# PCB.net
KiCad netlist of a schematic drawn in EasyEDA Pro
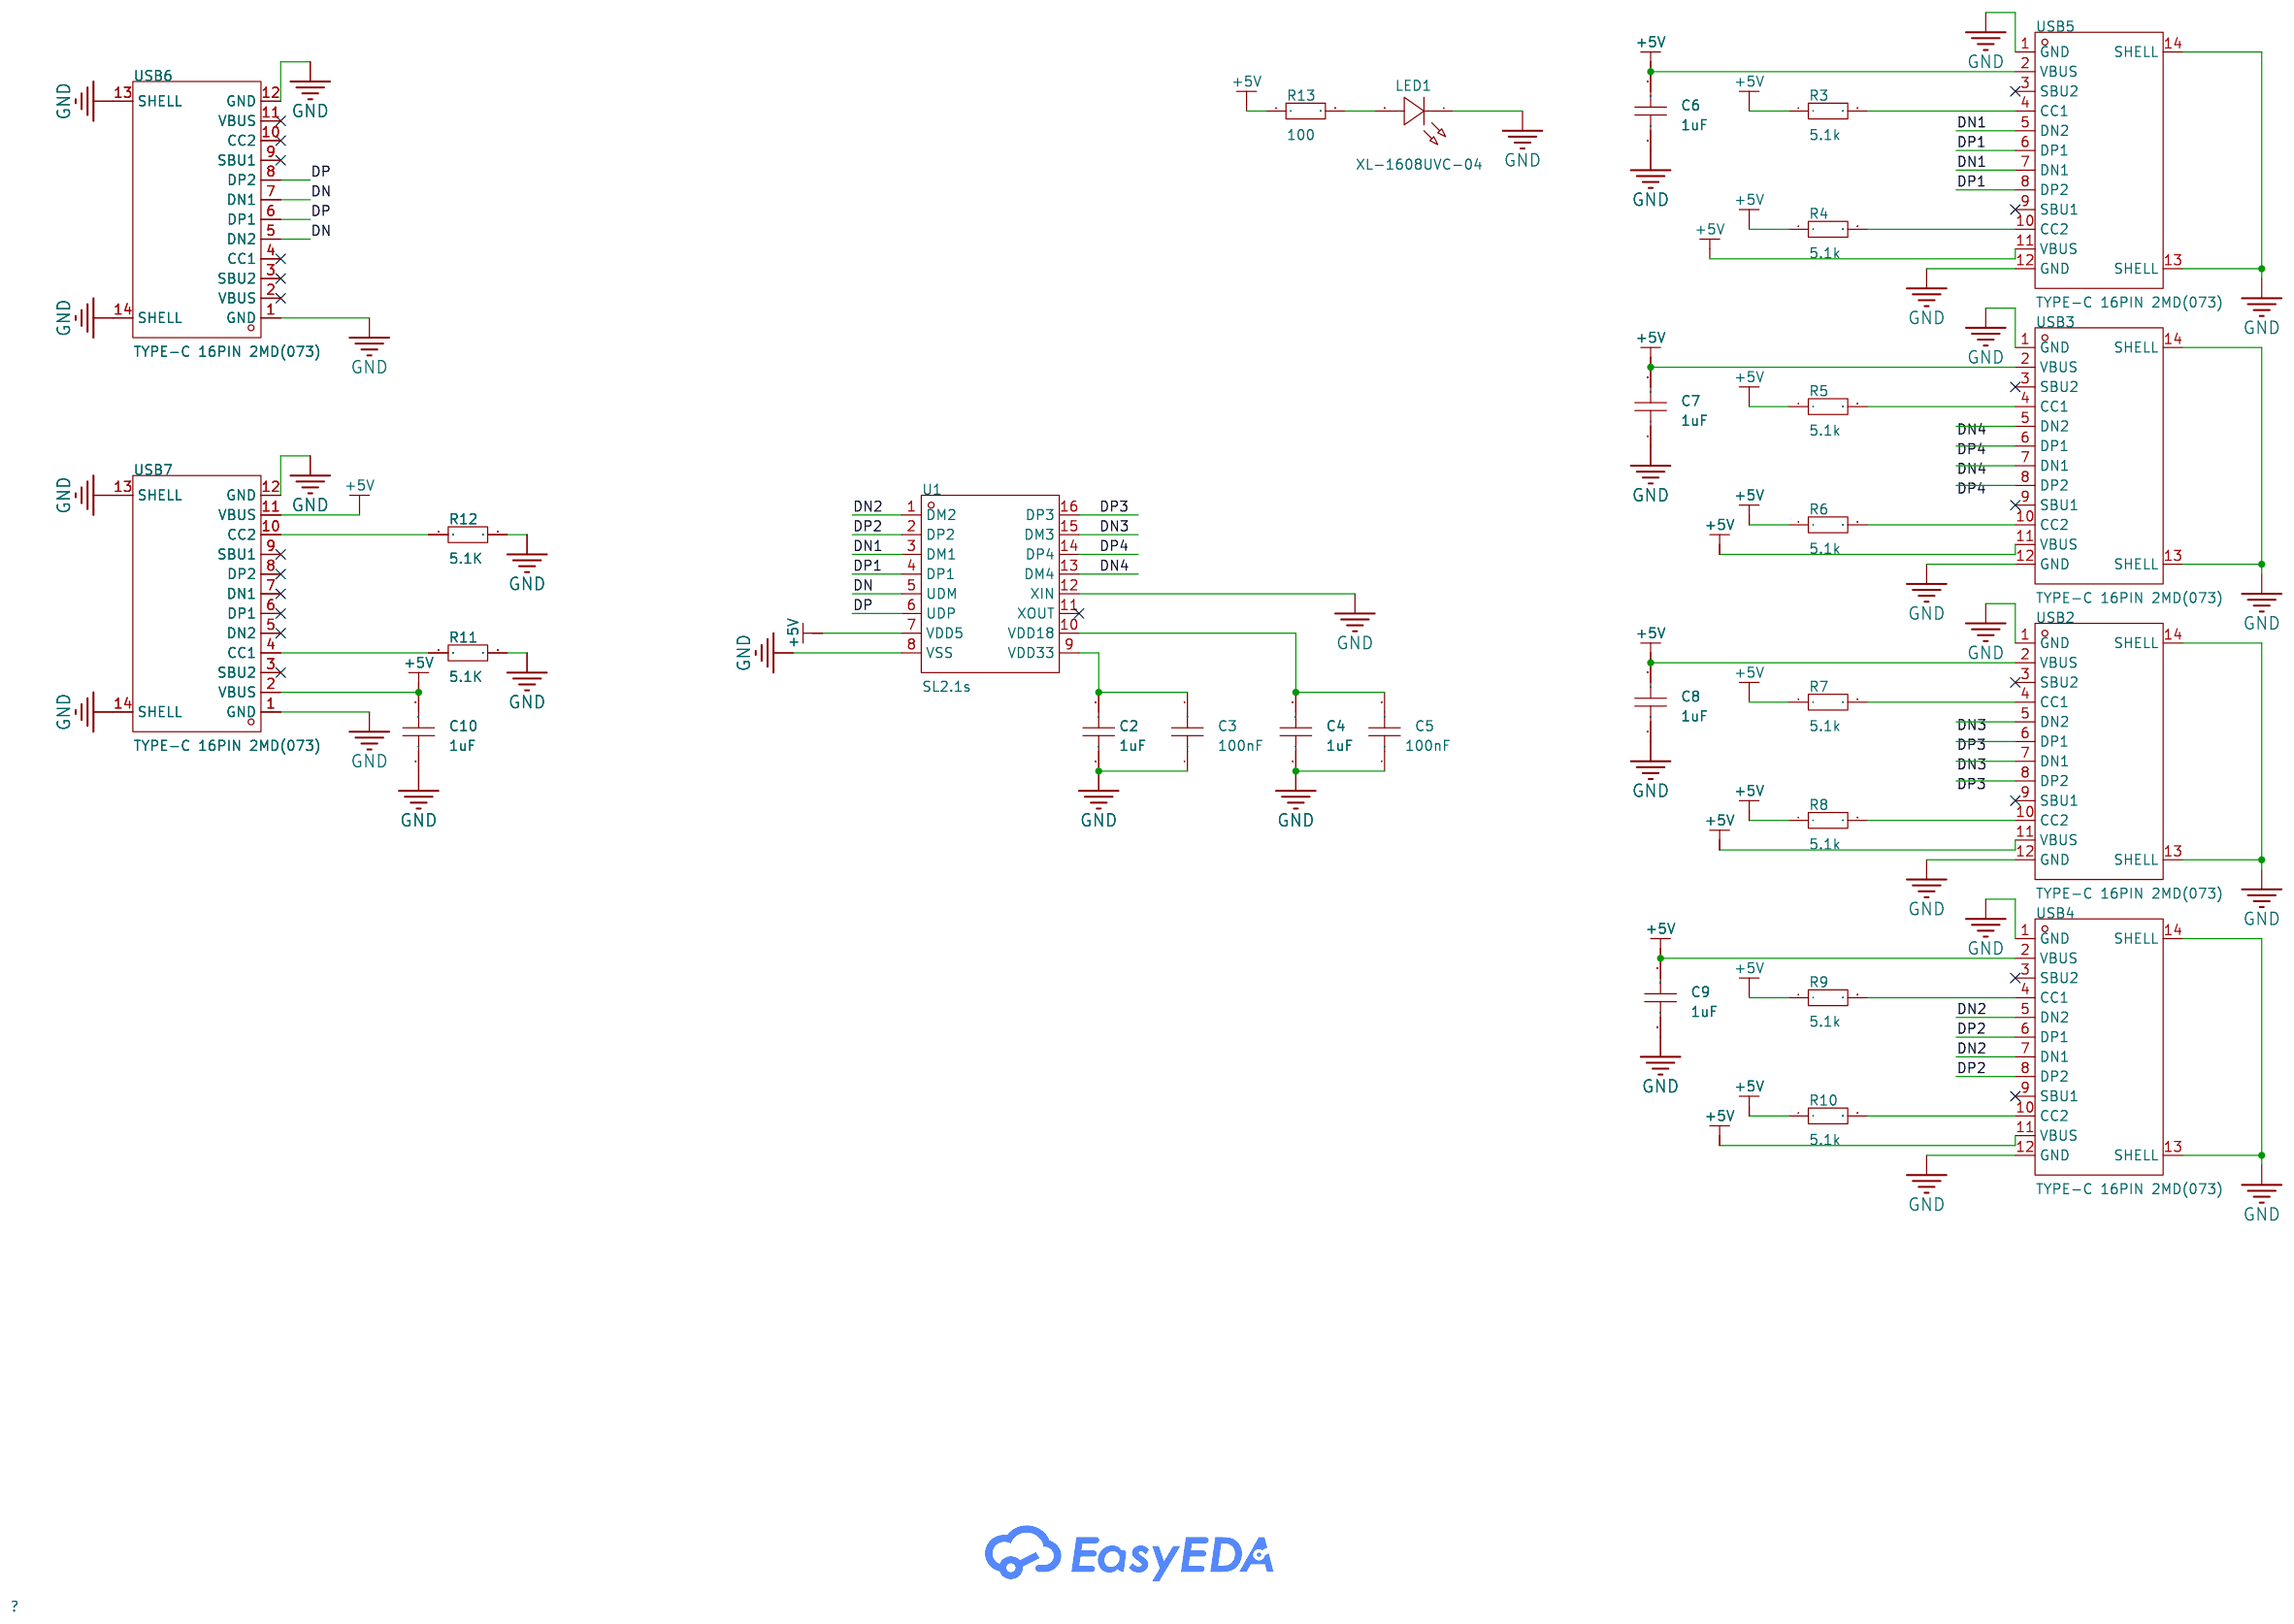
[diagram p0: schematic sheet]

(export (version "E")
  (design (tool "Eeschema 10.0.6"))
  (components
    (comp (ref "C2") (value "1uF") (footprint "easyedapro:C0603") (libsource (lib "easyedapro") (part "CAP")))
    (comp (ref "C3")
      (value "100nF")
      (footprint "easyedapro:C0603")
      (libsource (lib "easyedapro") (part "CAP"))
    )
    (comp (ref "C4") (value "1uF") (footprint "easyedapro:C0603") (libsource (lib "easyedapro") (part "CAP")))
    (comp (ref "C5")
      (value "100nF")
      (footprint "easyedapro:C0603")
      (libsource (lib "easyedapro") (part "CAP"))
    )
    (comp (ref "C6") (value "1uF") (footprint "easyedapro:C0603") (libsource (lib "easyedapro") (part "CAP")))
    (comp (ref "C7") (value "1uF") (footprint "easyedapro:C0603") (libsource (lib "easyedapro") (part "CAP")))
    (comp (ref "C8") (value "1uF") (footprint "easyedapro:C0603") (libsource (lib "easyedapro") (part "CAP")))
    (comp (ref "C9") (value "1uF") (footprint "easyedapro:C0603") (libsource (lib "easyedapro") (part "CAP")))
    (comp (ref "C10")
      (value "1uF")
      (footprint "easyedapro:C0603")
      (libsource (lib "easyedapro") (part "CAP"))
    )
    (comp (ref "LED1")
      (value "XL-1608UVC-04")
      (footprint "easyedapro:LED0603-RD_PINK")
      (fields (field (name "Manufacturer") "XINGLIGHT(成兴光)"))
      (libsource (lib "easyedapro") (part "XL-1608UVC-04"))
    )
    (comp (ref "R3")
      (value "5.1k")
      (footprint "easyedapro:R0603")
      (libsource (lib "easyedapro") (part "Res"))
    )
    (comp (ref "R4")
      (value "5.1k")
      (footprint "easyedapro:R0603")
      (libsource (lib "easyedapro") (part "Res"))
    )
    (comp (ref "R5")
      (value "5.1k")
      (footprint "easyedapro:R0603")
      (libsource (lib "easyedapro") (part "Res"))
    )
    (comp (ref "R6")
      (value "5.1k")
      (footprint "easyedapro:R0603")
      (libsource (lib "easyedapro") (part "Res"))
    )
    (comp (ref "R7")
      (value "5.1k")
      (footprint "easyedapro:R0603")
      (libsource (lib "easyedapro") (part "Res"))
    )
    (comp (ref "R8")
      (value "5.1k")
      (footprint "easyedapro:R0603")
      (libsource (lib "easyedapro") (part "Res"))
    )
    (comp (ref "R9")
      (value "5.1k")
      (footprint "easyedapro:R0603")
      (libsource (lib "easyedapro") (part "Res"))
    )
    (comp (ref "R10")
      (value "5.1k")
      (footprint "easyedapro:R0603")
      (libsource (lib "easyedapro") (part "Res"))
    )
    (comp (ref "R11")
      (value "10K")
      (footprint "easyedapro:R0603")
      (libsource (lib "easyedapro") (part "Res"))
    )
    (comp (ref "R12")
      (value "10K")
      (footprint "easyedapro:R0603")
      (libsource (lib "easyedapro") (part "Res"))
    )
    (comp (ref "R13")
      (value "100")
      (footprint "easyedapro:R0603")
      (libsource (lib "easyedapro") (part "Res"))
    )
    (comp (ref "U1")
      (value "SL2.1s")
      (footprint "easyedapro:SSOP-16_L4.6-W2.6-P0.53-LS4.0-BL")
      (fields (field (name "Manufacturer") "CoreChips(和芯润德)"))
      (libsource (lib "easyedapro") (part "SL2.1S"))
    )
    (comp (ref "USB2")
      (value "TYPE-C 16PIN 2MD(073)")
      (footprint "easyedapro:USB-C-SMD_TYPE-C-6PIN-2MD-073")
      (fields (field (name "Manufacturer") "SHOU HAN(首韩)"))
      (libsource (lib "easyedapro") (part "TYPE-C 16PIN 2MD(073)"))
    )
    (comp (ref "USB3")
      (value "TYPE-C 16PIN 2MD(073)")
      (footprint "easyedapro:USB-C-SMD_TYPE-C-6PIN-2MD-073")
      (fields (field (name "Manufacturer") "SHOU HAN(首韩)"))
      (libsource (lib "easyedapro") (part "TYPE-C 16PIN 2MD(073)"))
    )
    (comp (ref "USB4")
      (value "TYPE-C 16PIN 2MD(073)")
      (footprint "easyedapro:USB-C-SMD_TYPE-C-6PIN-2MD-073")
      (fields (field (name "Manufacturer") "SHOU HAN(首韩)"))
      (libsource (lib "easyedapro") (part "TYPE-C 16PIN 2MD(073)"))
    )
    (comp (ref "USB5")
      (value "TYPE-C 16PIN 2MD(073)")
      (footprint "easyedapro:USB-C-SMD_TYPE-C-6PIN-2MD-073")
      (fields (field (name "Manufacturer") "SHOU HAN(首韩)"))
      (libsource (lib "easyedapro") (part "TYPE-C 16PIN 2MD(073)"))
    )
    (comp (ref "USB6")
      (value "TYPE-C 16PIN 2MD(073)")
      (footprint "easyedapro:USB-C-SMD_TYPE-C-6PIN-2MD-073")
      (fields (field (name "Manufacturer") "SHOU HAN(首韩)"))
      (libsource (lib "easyedapro") (part "TYPE-C 16PIN 2MD(073)"))
    )
    (comp (ref "USB7")
      (value "TYPE-C 16PIN 2MD(073)")
      (footprint "easyedapro:USB-C-SMD_TYPE-C-6PIN-2MD-073")
      (fields (field (name "Manufacturer") "SHOU HAN(首韩)"))
      (libsource (lib "easyedapro") (part "TYPE-C 16PIN 2MD(073)"))
    )
  )
  (nets
    (net (code "1") (name "+5V") (class "Default")
      (node (ref "C10") (pin "2") (pinfunction "2_2") (pintype "input"))
      (node (ref "C6") (pin "2") (pinfunction "2_2") (pintype "input"))
      (node (ref "C7") (pin "2") (pinfunction "2_2") (pintype "input"))
      (node (ref "C8") (pin "2") (pinfunction "2_2") (pintype "input"))
      (node (ref "C9") (pin "2") (pinfunction "2_2") (pintype "input"))
      (node (ref "R10") (pin "1") (pinfunction "1_1") (pintype "input"))
      (node (ref "R13") (pin "1") (pinfunction "1_1") (pintype "input"))
      (node (ref "R3") (pin "1") (pinfunction "1_1") (pintype "input"))
      (node (ref "R4") (pin "1") (pinfunction "1_1") (pintype "input"))
      (node (ref "R5") (pin "1") (pinfunction "1_1") (pintype "input"))
      (node (ref "R6") (pin "1") (pinfunction "1_1") (pintype "input"))
      (node (ref "R7") (pin "1") (pinfunction "1_1") (pintype "input"))
      (node (ref "R8") (pin "1") (pinfunction "1_1") (pintype "input"))
      (node (ref "R9") (pin "1") (pinfunction "1_1") (pintype "input"))
      (node (ref "U1") (pin "7") (pinfunction "VDD5_7") (pintype "unspecified"))
      (node (ref "USB2") (pin "11") (pinfunction "VBUS_11") (pintype "unspecified"))
      (node (ref "USB2") (pin "2") (pinfunction "VBUS_2") (pintype "unspecified"))
      (node (ref "USB3") (pin "11") (pinfunction "VBUS_11") (pintype "unspecified"))
      (node (ref "USB3") (pin "2") (pinfunction "VBUS_2") (pintype "unspecified"))
      (node (ref "USB4") (pin "11") (pinfunction "VBUS_11") (pintype "unspecified"))
      (node (ref "USB4") (pin "2") (pinfunction "VBUS_2") (pintype "unspecified"))
      (node (ref "USB5") (pin "11") (pinfunction "VBUS_11") (pintype "unspecified"))
      (node (ref "USB5") (pin "2") (pinfunction "VBUS_2") (pintype "unspecified"))
      (node (ref "USB7") (pin "11") (pinfunction "VBUS_11") (pintype "unspecified"))
      (node (ref "USB7") (pin "2") (pinfunction "VBUS_2") (pintype "unspecified"))
    )
    (net (code "2") (name "/DN") (class "Default")
      (node (ref "U1") (pin "5") (pinfunction "UDM_5") (pintype "unspecified"))
      (node (ref "USB6") (pin "5") (pinfunction "DN2_5") (pintype "unspecified"))
      (node (ref "USB6") (pin "7") (pinfunction "DN1_7") (pintype "unspecified"))
    )
    (net (code "3") (name "/DN1") (class "Default")
      (node (ref "U1") (pin "3") (pinfunction "DM1_3") (pintype "unspecified"))
      (node (ref "USB5") (pin "5") (pinfunction "DN2_5") (pintype "unspecified"))
      (node (ref "USB5") (pin "7") (pinfunction "DN1_7") (pintype "unspecified"))
    )
    (net (code "4") (name "/DN2") (class "Default")
      (node (ref "U1") (pin "1") (pinfunction "DM2_1") (pintype "unspecified"))
      (node (ref "USB4") (pin "5") (pinfunction "DN2_5") (pintype "unspecified"))
      (node (ref "USB4") (pin "7") (pinfunction "DN1_7") (pintype "unspecified"))
    )
    (net (code "5") (name "/DN3") (class "Default")
      (node (ref "U1") (pin "15") (pinfunction "DM3_15") (pintype "unspecified"))
      (node (ref "USB2") (pin "5") (pinfunction "DN2_5") (pintype "unspecified"))
      (node (ref "USB2") (pin "7") (pinfunction "DN1_7") (pintype "unspecified"))
    )
    (net (code "6") (name "/DN4") (class "Default")
      (node (ref "U1") (pin "13") (pinfunction "DM4_13") (pintype "unspecified"))
      (node (ref "USB3") (pin "5") (pinfunction "DN2_5") (pintype "unspecified"))
      (node (ref "USB3") (pin "7") (pinfunction "DN1_7") (pintype "unspecified"))
    )
    (net (code "7") (name "/DP") (class "Default")
      (node (ref "U1") (pin "6") (pinfunction "UDP_6") (pintype "unspecified"))
      (node (ref "USB6") (pin "6") (pinfunction "DP1_6") (pintype "unspecified"))
      (node (ref "USB6") (pin "8") (pinfunction "DP2_8") (pintype "unspecified"))
    )
    (net (code "8") (name "/DP1") (class "Default")
      (node (ref "U1") (pin "4") (pinfunction "DP1_4") (pintype "unspecified"))
      (node (ref "USB5") (pin "6") (pinfunction "DP1_6") (pintype "unspecified"))
      (node (ref "USB5") (pin "8") (pinfunction "DP2_8") (pintype "unspecified"))
    )
    (net (code "9") (name "/DP2") (class "Default")
      (node (ref "U1") (pin "2") (pinfunction "DP2_2") (pintype "unspecified"))
      (node (ref "USB4") (pin "6") (pinfunction "DP1_6") (pintype "unspecified"))
      (node (ref "USB4") (pin "8") (pinfunction "DP2_8") (pintype "unspecified"))
    )
    (net (code "10") (name "/DP3") (class "Default")
      (node (ref "U1") (pin "16") (pinfunction "DP3_16") (pintype "unspecified"))
      (node (ref "USB2") (pin "6") (pinfunction "DP1_6") (pintype "unspecified"))
      (node (ref "USB2") (pin "8") (pinfunction "DP2_8") (pintype "unspecified"))
    )
    (net (code "11") (name "/DP4") (class "Default")
      (node (ref "U1") (pin "14") (pinfunction "DP4_14") (pintype "unspecified"))
      (node (ref "USB3") (pin "6") (pinfunction "DP1_6") (pintype "unspecified"))
      (node (ref "USB3") (pin "8") (pinfunction "DP2_8") (pintype "unspecified"))
    )
    (net (code "12") (name "GND") (class "Default")
      (node (ref "C10") (pin "1") (pinfunction "1_1") (pintype "input"))
      (node (ref "C2") (pin "1") (pinfunction "1_1") (pintype "input"))
      (node (ref "C3") (pin "1") (pinfunction "1_1") (pintype "input"))
      (node (ref "C4") (pin "1") (pinfunction "1_1") (pintype "input"))
      (node (ref "C5") (pin "1") (pinfunction "1_1") (pintype "input"))
      (node (ref "C6") (pin "1") (pinfunction "1_1") (pintype "input"))
      (node (ref "C7") (pin "1") (pinfunction "1_1") (pintype "input"))
      (node (ref "C8") (pin "1") (pinfunction "1_1") (pintype "input"))
      (node (ref "C9") (pin "1") (pinfunction "1_1") (pintype "input"))
      (node (ref "LED1") (pin "1") (pinfunction "K_1") (pintype "unspecified"))
      (node (ref "R11") (pin "2") (pinfunction "2_2") (pintype "input"))
      (node (ref "R12") (pin "2") (pinfunction "2_2") (pintype "input"))
      (node (ref "U1") (pin "12") (pinfunction "XIN_12") (pintype "unspecified"))
      (node (ref "U1") (pin "8") (pinfunction "VSS_8") (pintype "unspecified"))
      (node (ref "USB2") (pin "1") (pinfunction "GND_1") (pintype "unspecified"))
      (node (ref "USB2") (pin "12") (pinfunction "GND_12") (pintype "unspecified"))
      (node (ref "USB2") (pin "13") (pinfunction "SHELL_13") (pintype "unspecified"))
      (node (ref "USB2") (pin "14") (pinfunction "SHELL_14") (pintype "unspecified"))
      (node (ref "USB3") (pin "1") (pinfunction "GND_1") (pintype "unspecified"))
      (node (ref "USB3") (pin "12") (pinfunction "GND_12") (pintype "unspecified"))
      (node (ref "USB3") (pin "13") (pinfunction "SHELL_13") (pintype "unspecified"))
      (node (ref "USB3") (pin "14") (pinfunction "SHELL_14") (pintype "unspecified"))
      (node (ref "USB4") (pin "1") (pinfunction "GND_1") (pintype "unspecified"))
      (node (ref "USB4") (pin "12") (pinfunction "GND_12") (pintype "unspecified"))
      (node (ref "USB4") (pin "13") (pinfunction "SHELL_13") (pintype "unspecified"))
      (node (ref "USB4") (pin "14") (pinfunction "SHELL_14") (pintype "unspecified"))
      (node (ref "USB5") (pin "1") (pinfunction "GND_1") (pintype "unspecified"))
      (node (ref "USB5") (pin "12") (pinfunction "GND_12") (pintype "unspecified"))
      (node (ref "USB5") (pin "13") (pinfunction "SHELL_13") (pintype "unspecified"))
      (node (ref "USB5") (pin "14") (pinfunction "SHELL_14") (pintype "unspecified"))
      (node (ref "USB6") (pin "1") (pinfunction "GND_1") (pintype "unspecified"))
      (node (ref "USB6") (pin "12") (pinfunction "GND_12") (pintype "unspecified"))
      (node (ref "USB6") (pin "13") (pinfunction "SHELL_13") (pintype "unspecified"))
      (node (ref "USB6") (pin "14") (pinfunction "SHELL_14") (pintype "unspecified"))
      (node (ref "USB7") (pin "1") (pinfunction "GND_1") (pintype "unspecified"))
      (node (ref "USB7") (pin "12") (pinfunction "GND_12") (pintype "unspecified"))
      (node (ref "USB7") (pin "13") (pinfunction "SHELL_13") (pintype "unspecified"))
      (node (ref "USB7") (pin "14") (pinfunction "SHELL_14") (pintype "unspecified"))
    )
    (net (code "13") (name "Net-(LED1-A)") (class "Default")
      (node (ref "LED1") (pin "2") (pinfunction "A_2") (pintype "unspecified"))
      (node (ref "R13") (pin "2") (pinfunction "2_2") (pintype "input"))
    )
    (net (code "14") (name "Net-(U1-VDD18)") (class "Default")
      (node (ref "C4") (pin "2") (pinfunction "2_2") (pintype "input"))
      (node (ref "C5") (pin "2") (pinfunction "2_2") (pintype "input"))
      (node (ref "U1") (pin "10") (pinfunction "VDD18_10") (pintype "unspecified"))
    )
    (net (code "15") (name "Net-(U1-VDD33)") (class "Default")
      (node (ref "C2") (pin "2") (pinfunction "2_2") (pintype "input"))
      (node (ref "C3") (pin "2") (pinfunction "2_2") (pintype "input"))
      (node (ref "U1") (pin "9") (pinfunction "VDD33_9") (pintype "unspecified"))
    )
    (net (code "16") (name "Net-(USB2-CC1)") (class "Default")
      (node (ref "R7") (pin "2") (pinfunction "2_2") (pintype "input"))
      (node (ref "USB2") (pin "4") (pinfunction "CC1_4") (pintype "unspecified"))
    )
    (net (code "17") (name "Net-(USB2-CC2)") (class "Default")
      (node (ref "R8") (pin "2") (pinfunction "2_2") (pintype "input"))
      (node (ref "USB2") (pin "10") (pinfunction "CC2_10") (pintype "unspecified"))
    )
    (net (code "18") (name "Net-(USB3-CC1)") (class "Default")
      (node (ref "R5") (pin "2") (pinfunction "2_2") (pintype "input"))
      (node (ref "USB3") (pin "4") (pinfunction "CC1_4") (pintype "unspecified"))
    )
    (net (code "19") (name "Net-(USB3-CC2)") (class "Default")
      (node (ref "R6") (pin "2") (pinfunction "2_2") (pintype "input"))
      (node (ref "USB3") (pin "10") (pinfunction "CC2_10") (pintype "unspecified"))
    )
    (net (code "20") (name "Net-(USB4-CC1)") (class "Default")
      (node (ref "R9") (pin "2") (pinfunction "2_2") (pintype "input"))
      (node (ref "USB4") (pin "4") (pinfunction "CC1_4") (pintype "unspecified"))
    )
    (net (code "21") (name "Net-(USB4-CC2)") (class "Default")
      (node (ref "R10") (pin "2") (pinfunction "2_2") (pintype "input"))
      (node (ref "USB4") (pin "10") (pinfunction "CC2_10") (pintype "unspecified"))
    )
    (net (code "22") (name "Net-(USB5-CC1)") (class "Default")
      (node (ref "R3") (pin "2") (pinfunction "2_2") (pintype "input"))
      (node (ref "USB5") (pin "4") (pinfunction "CC1_4") (pintype "unspecified"))
    )
    (net (code "23") (name "Net-(USB5-CC2)") (class "Default")
      (node (ref "R4") (pin "2") (pinfunction "2_2") (pintype "input"))
      (node (ref "USB5") (pin "10") (pinfunction "CC2_10") (pintype "unspecified"))
    )
    (net (code "24") (name "Net-(USB7-CC1)") (class "Default")
      (node (ref "R11") (pin "1") (pinfunction "1_1") (pintype "input"))
      (node (ref "USB7") (pin "4") (pinfunction "CC1_4") (pintype "unspecified"))
    )
    (net (code "25") (name "Net-(USB7-CC2)") (class "Default")
      (node (ref "R12") (pin "1") (pinfunction "1_1") (pintype "input"))
      (node (ref "USB7") (pin "10") (pinfunction "CC2_10") (pintype "unspecified"))
    )
    (net (code "26") (name "unconnected-(U1-XOUT-Pad11)") (class "Default")
      (node (ref "U1") (pin "11") (pinfunction "XOUT_11") (pintype "unspecified+no_connect"))
    )
    (net (code "27") (name "unconnected-(USB2-SBU1-Pad9)") (class "Default")
      (node (ref "USB2") (pin "9") (pinfunction "SBU1_9") (pintype "unspecified+no_connect"))
    )
    (net (code "28") (name "unconnected-(USB2-SBU2-Pad3)") (class "Default")
      (node (ref "USB2") (pin "3") (pinfunction "SBU2_3") (pintype "unspecified+no_connect"))
    )
    (net (code "29") (name "unconnected-(USB3-SBU1-Pad9)") (class "Default")
      (node (ref "USB3") (pin "9") (pinfunction "SBU1_9") (pintype "unspecified+no_connect"))
    )
    (net (code "30") (name "unconnected-(USB3-SBU2-Pad3)") (class "Default")
      (node (ref "USB3") (pin "3") (pinfunction "SBU2_3") (pintype "unspecified+no_connect"))
    )
    (net (code "31") (name "unconnected-(USB4-SBU1-Pad9)") (class "Default")
      (node (ref "USB4") (pin "9") (pinfunction "SBU1_9") (pintype "unspecified+no_connect"))
    )
    (net (code "32") (name "unconnected-(USB4-SBU2-Pad3)") (class "Default")
      (node (ref "USB4") (pin "3") (pinfunction "SBU2_3") (pintype "unspecified+no_connect"))
    )
    (net (code "33") (name "unconnected-(USB5-SBU1-Pad9)") (class "Default")
      (node (ref "USB5") (pin "9") (pinfunction "SBU1_9") (pintype "unspecified+no_connect"))
    )
    (net (code "34") (name "unconnected-(USB5-SBU2-Pad3)") (class "Default")
      (node (ref "USB5") (pin "3") (pinfunction "SBU2_3") (pintype "unspecified+no_connect"))
    )
    (net (code "35") (name "unconnected-(USB6-CC1-Pad4)") (class "Default")
      (node (ref "USB6") (pin "4") (pinfunction "CC1_4") (pintype "unspecified+no_connect"))
    )
    (net (code "36") (name "unconnected-(USB6-CC2-Pad10)") (class "Default")
      (node (ref "USB6") (pin "10") (pinfunction "CC2_10") (pintype "unspecified+no_connect"))
    )
    (net (code "37") (name "unconnected-(USB6-SBU1-Pad9)") (class "Default")
      (node (ref "USB6") (pin "9") (pinfunction "SBU1_9") (pintype "unspecified+no_connect"))
    )
    (net (code "38") (name "unconnected-(USB6-SBU2-Pad3)") (class "Default")
      (node (ref "USB6") (pin "3") (pinfunction "SBU2_3") (pintype "unspecified+no_connect"))
    )
    (net (code "39") (name "unconnected-(USB6-VBUS-Pad2)") (class "Default")
      (node (ref "USB6") (pin "2") (pinfunction "VBUS_2") (pintype "unspecified+no_connect"))
    )
    (net (code "40") (name "unconnected-(USB6-VBUS-Pad11)") (class "Default")
      (node (ref "USB6") (pin "11") (pinfunction "VBUS_11") (pintype "unspecified+no_connect"))
    )
    (net (code "41") (name "unconnected-(USB7-DN1-Pad7)") (class "Default")
      (node (ref "USB7") (pin "7") (pinfunction "DN1_7") (pintype "unspecified+no_connect"))
    )
    (net (code "42") (name "unconnected-(USB7-DN2-Pad5)") (class "Default")
      (node (ref "USB7") (pin "5") (pinfunction "DN2_5") (pintype "unspecified+no_connect"))
    )
    (net (code "43") (name "unconnected-(USB7-DP1-Pad6)") (class "Default")
      (node (ref "USB7") (pin "6") (pinfunction "DP1_6") (pintype "unspecified+no_connect"))
    )
    (net (code "44") (name "unconnected-(USB7-DP2-Pad8)") (class "Default")
      (node (ref "USB7") (pin "8") (pinfunction "DP2_8") (pintype "unspecified+no_connect"))
    )
    (net (code "45") (name "unconnected-(USB7-SBU1-Pad9)") (class "Default")
      (node (ref "USB7") (pin "9") (pinfunction "SBU1_9") (pintype "unspecified+no_connect"))
    )
    (net (code "46") (name "unconnected-(USB7-SBU2-Pad3)") (class "Default")
      (node (ref "USB7") (pin "3") (pinfunction "SBU2_3") (pintype "unspecified+no_connect"))
    )
  )
)
